# Main_Power_Switch.net
KiCad netlist of a schematic drawn in Altium Designer
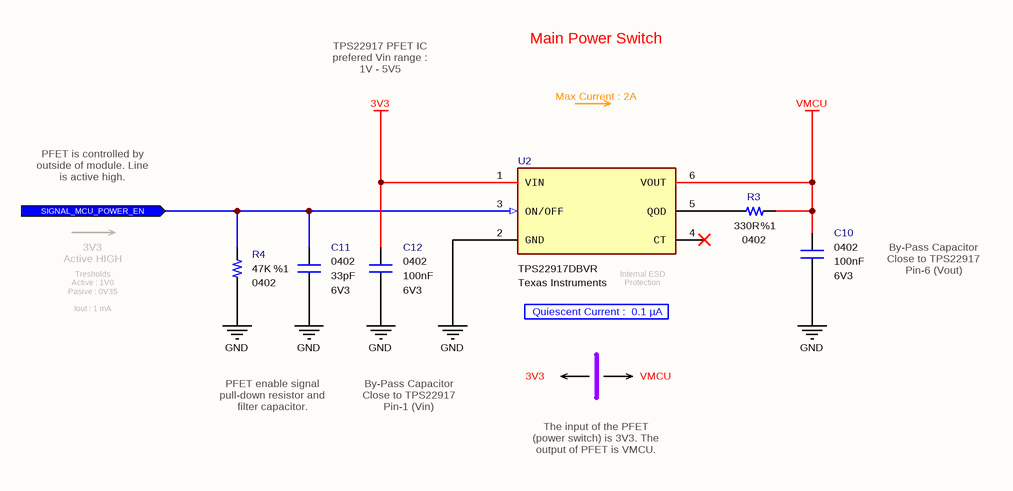
[diagram p0: Main Power Switch.SchDoc]

(export (version "E")
  (design (tool "Eeschema 10.0.6"))
  (components
    (comp (ref "C10")
      (value "100nF")
      (footprint "CAPACITOR_0402")
      (description "Capacitor - 100nF [0402-6V3] (Ceramic)")
      (fields
        (field (name "TOLERANCE") "%10")
        (field (name "CASE") "0402")
        (field (name "VOLTAGE") "6V3")
        (field (name "MANUFACTURER PART NUMBER") "04026D104KAT4A")
      )
      (libsource (lib "Ovoo_Library") (part "Capacitor - 100nF [0402-6V3]"))
    )
    (comp (ref "C11")
      (value "33pF")
      (footprint "CAPACITOR_0402")
      (description "Capacitor - 33pF [0402] (Ceramic)")
      (fields
        (field (name "TOLERANCE") "10%")
        (field (name "CASE") "0402")
        (field (name "VOLTAGE") "6V3")
        (field (name "MANUFACTURER PART NUMBER") "C0402C330J9RACAUTO")
      )
      (libsource (lib "Ovoo_Library") (part "Capacitor - 33pF [0402-6V3]"))
    )
    (comp (ref "C12")
      (value "100nF")
      (footprint "CAPACITOR_0402")
      (description "Capacitor - 100nF [0402-6V3] (Ceramic)")
      (fields
        (field (name "CASE") "0402")
        (field (name "TOLERANCE") "%10")
        (field (name "VOLTAGE") "6V3")
        (field (name "MANUFACTURER PART NUMBER") "04026D104KAT4A")
      )
      (libsource (lib "Ovoo_Library") (part "Capacitor - 100nF [0402-6V3]"))
    )
    (comp (ref "R3")
      (value "330R")
      (footprint "RESISTOR_0402")
      (description "Thick Film Resistors - SMD 1/16 W 330 Ohm 1%")
      (fields
        (field (name "TOLERANCE") "%1")
        (field (name "CASE") "0402")
        (field (name "MANUFACTURER PART NUMBER") "CRCW0402330RFKED")
        (field (name "MOUSER PART NUMBER") "71-CRCW0402-330-E3")
      )
      (libsource (lib "Ovoo_Library") (part "Resistor - 330R"))
    )
    (comp (ref "R4")
      (value "47K")
      (footprint "RESISTOR_0402")
      (description "Thick Film Resistors - SMD 1/16 W 47 Kohms 1%")
      (fields
        (field (name "TOLERANCE") "%1")
        (field (name "CASE") "0402")
        (field (name "MANUFACTURER PART NUMBER") "CRCW040247K0FKED")
        (field (name "Comment") "47K - 0402 - %1 - 1/16W")
      )
      (libsource (lib "Ovoo_Library") (part "Resistor - 47K"))
    )
    (comp (ref "U2")
      (value "Power Switch")
      (footprint "SOT-23-6")
      (description "Power Switch MosFet")
      (fields
        (field (name "MOUSER PART NUMBER") "595-TPS22917DBVR")
        (field (name "MANUFACTURER PART NUMBER") "TPS22917DBVR")
        (field (name "MANUFACTURER NAME") "Texas Instruments")
      )
      (libsource (lib "Ovoo_Library") (part "IC - TPS22917DBVR"))
    )
  )
  (nets
    (net (code "1") (name "/SIGNAL_MCU_POWER_EN") (class "Default")
      (node (ref "C11") (pin "2") (pinfunction "2_2") (pintype "passive"))
      (node (ref "R4") (pin "2") (pinfunction "2_2") (pintype "passive"))
      (node (ref "U2") (pin "3") (pinfunction "ON/OFF_3") (pintype "input"))
    )
    (net (code "2") (name "3V3") (class "Default")
      (node (ref "C12") (pin "1") (pinfunction "1_1") (pintype "passive"))
      (node (ref "U2") (pin "1") (pinfunction "VIN_1") (pintype "power_in"))
    )
    (net (code "3") (name "GND") (class "Default")
      (node (ref "C10") (pin "2") (pinfunction "2_2") (pintype "passive"))
      (node (ref "C11") (pin "1") (pinfunction "1_1") (pintype "passive"))
      (node (ref "C12") (pin "2") (pinfunction "2_2") (pintype "passive"))
      (node (ref "R4") (pin "1") (pinfunction "1_1") (pintype "passive"))
      (node (ref "U2") (pin "2") (pinfunction "GND_2") (pintype "power_in"))
    )
    (net (code "4") (name "Net-(U2-QOD)") (class "Default")
      (node (ref "R3") (pin "2") (pinfunction "2_2") (pintype "passive"))
      (node (ref "U2") (pin "5") (pinfunction "QOD_5") (pintype "power_in"))
    )
    (net (code "5") (name "VMCU") (class "Default")
      (node (ref "C10") (pin "1") (pinfunction "1_1") (pintype "passive"))
      (node (ref "R3") (pin "1") (pinfunction "1_1") (pintype "passive"))
      (node (ref "U2") (pin "6") (pinfunction "VOUT_6") (pintype "power_in"))
    )
    (net (code "6") (name "unconnected-(U2-CT-Pad4)") (class "Default")
      (node (ref "U2") (pin "4") (pinfunction "CT_4") (pintype "power_in+no_connect"))
    )
  )
)
